# PAPR_STM32G031J6_V1.net
KiCad netlist of a schematic drawn in EasyEDA
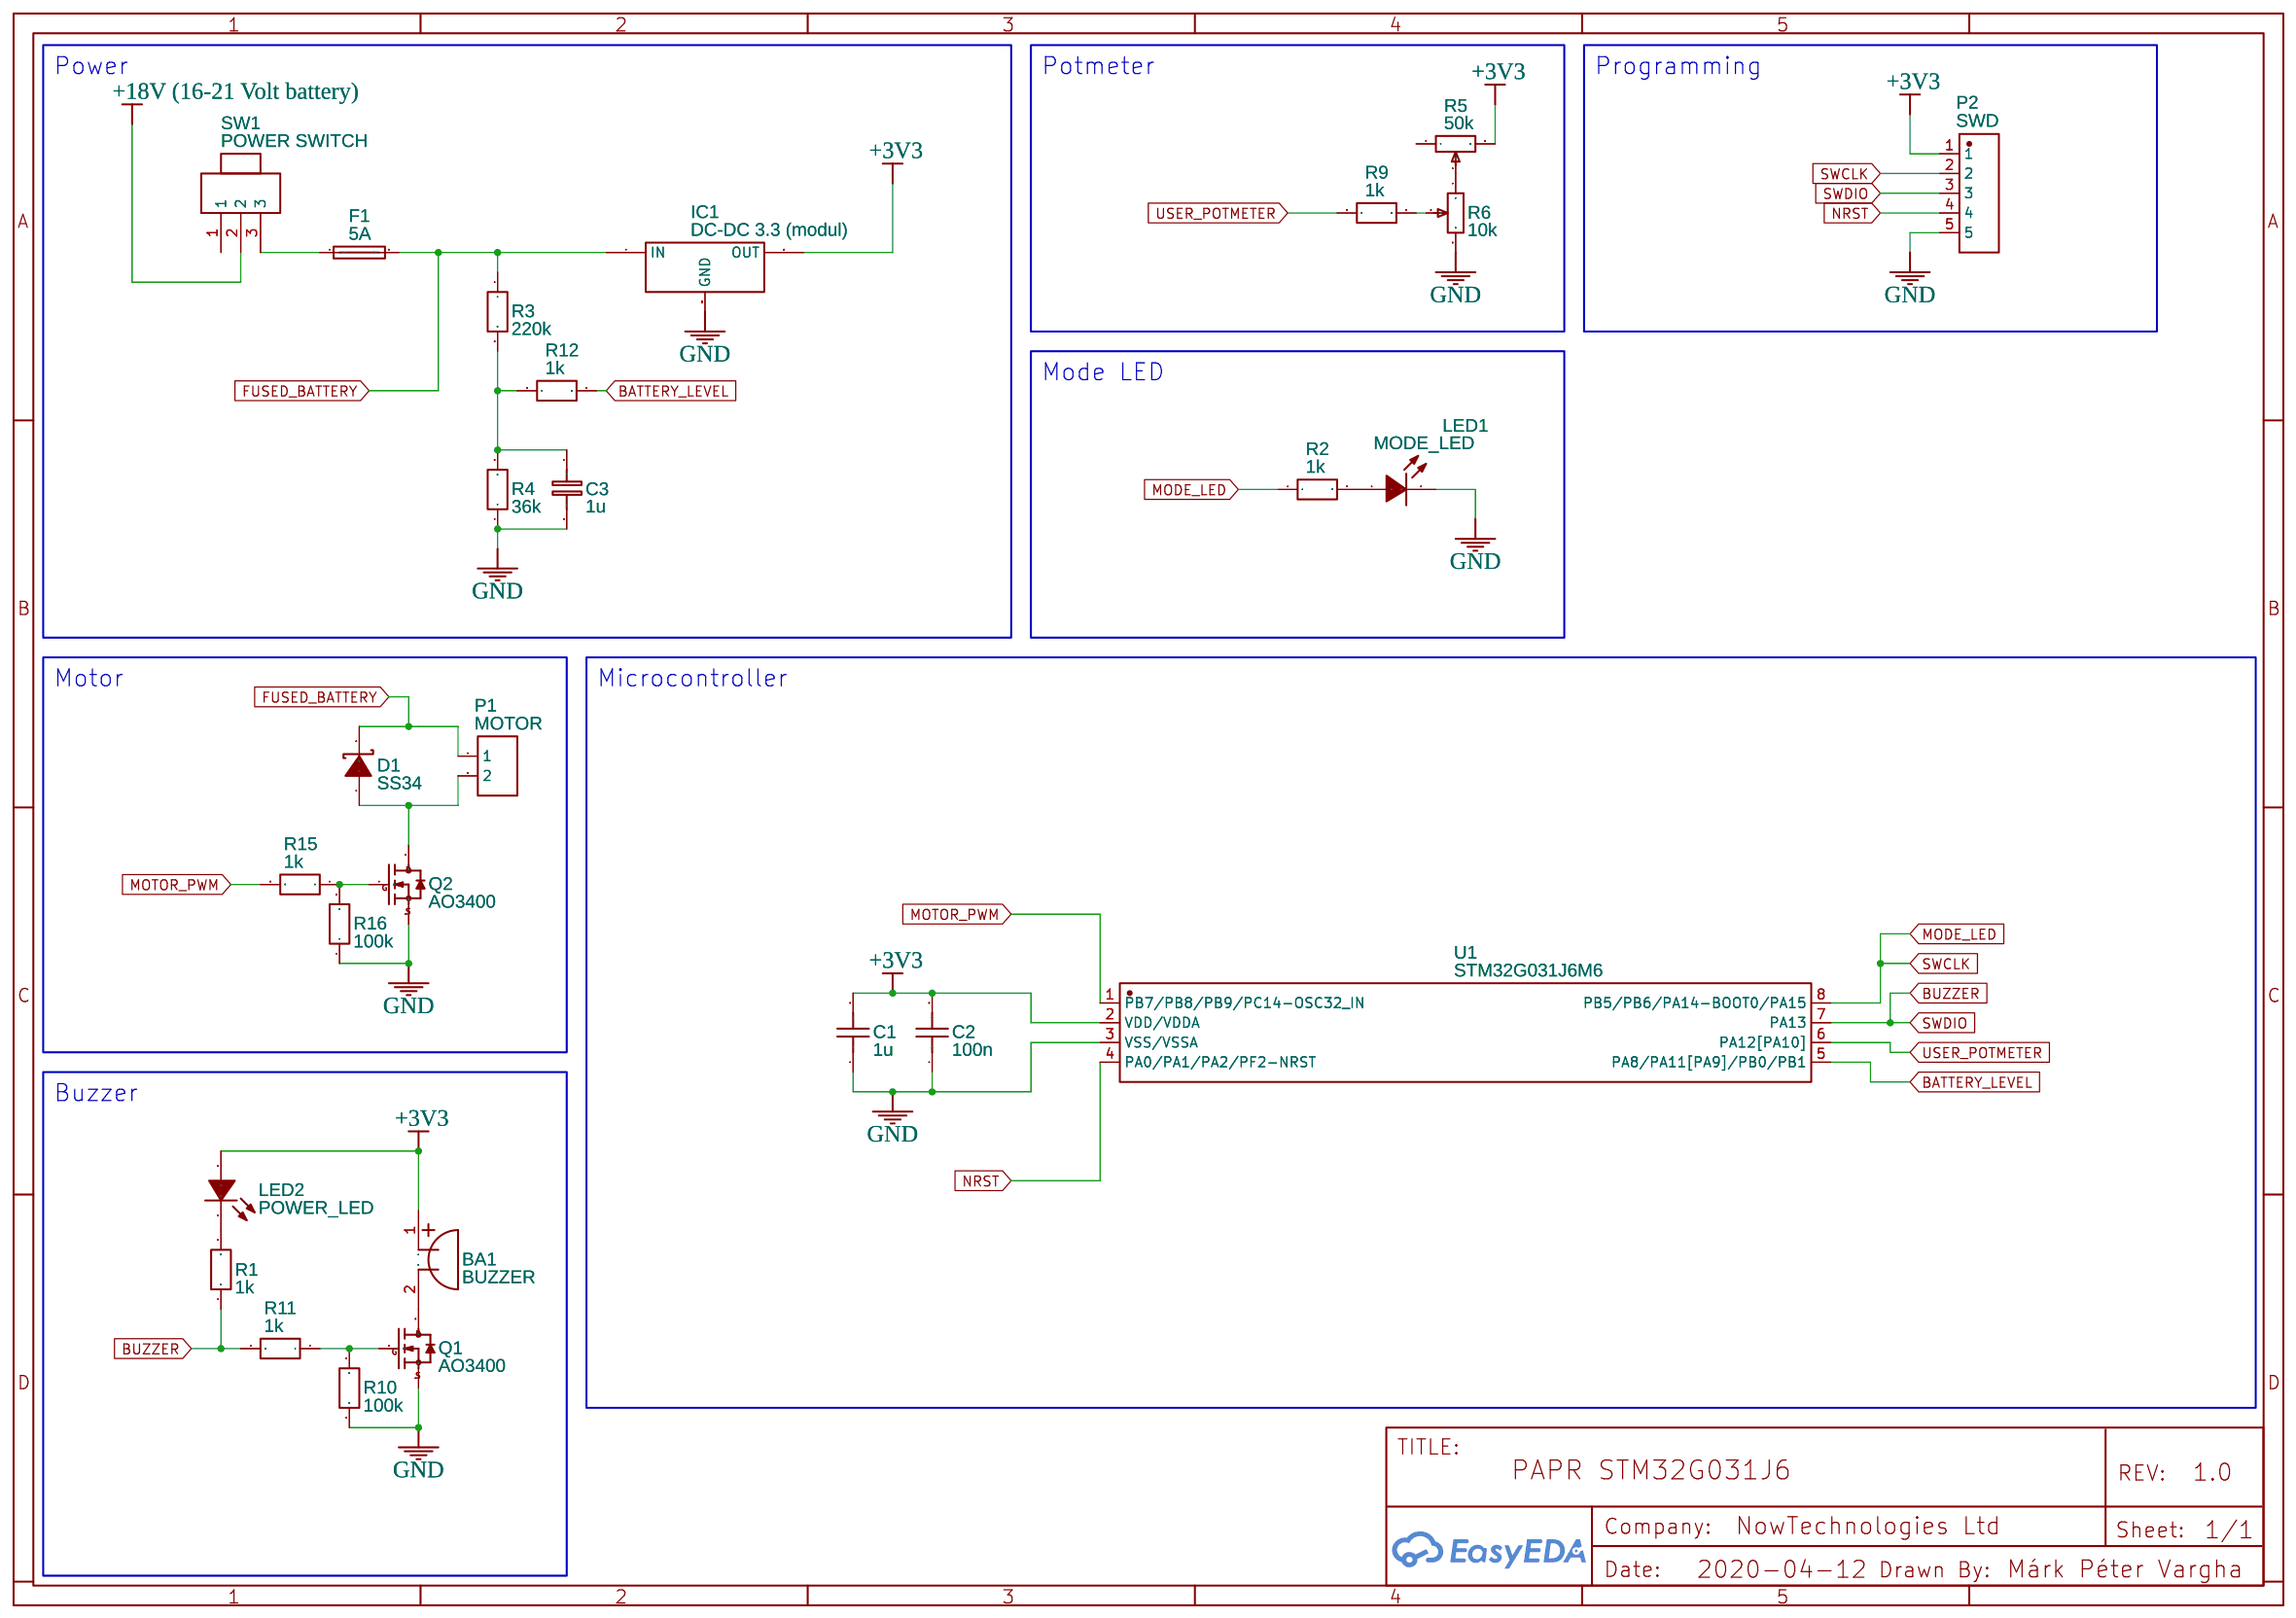
[diagram p0: schematic sheet]

(export (version "E")
  (design (tool "Eeschema 10.0.6"))
  (components
    (comp (ref "BA1") (value "BUZZER") (libsource (lib "") (part "9X5.5_BEEPER_5V")))
    (comp (ref "C1") (value "1u") (libsource (lib "") (part "Cap_RAD-0.1_US")))
    (comp (ref "C2") (value "100n") (libsource (lib "") (part "Cap_RAD-0.1_US")))
    (comp (ref "C3") (value "1u") (libsource (lib "") (part "Cap_RAD-0.1_EU")))
    (comp (ref "D1")
      (value "SS34")
      (fields (field (name "BOM_Supplier Part") "C13763"))
      (libsource (lib "") (part "SS34"))
    )
    (comp (ref "F1")
      (value "5A")
      (fields
        (field (name "BOM_Manufacturer Part") "5F 5A 250VACGlass tube fuse")
        (field (name "BOM_Supplier Part") "C3120")
      )
      (libsource (lib "") (part "5F 5A 250VACGlass tube fuse"))
    )
    (comp (ref "IC1") (value "DC-DC 3.3 (modul)") (libsource (lib "") (part "AMS1117 3.3")))
    (comp (ref "LED1")
      (value "MODE_LED")
      (fields
        (field (name "BOM_Manufacturer Part") "204-10SURD/S530-A3")
        (field (name "BOM_Supplier Part") "C99772")
      )
      (libsource (lib "") (part "204-10SURD/S530-A3_1"))
    )
    (comp (ref "LED2")
      (value "POWER_LED")
      (fields
        (field (name "BOM_Manufacturer Part") "204-10SURD/S530-A3")
        (field (name "BOM_Supplier Part") "C99772")
      )
      (libsource (lib "") (part "204-10SURD/S530-A3"))
    )
    (comp (ref "P1")
      (value "MOTOR")
      (fields
        (field (name "BOM_Manufacturer Part") "2.54-1*2PFemale")
        (field (name "BOM_Supplier Part") "C49661")
      )
      (libsource (lib "") (part "Header-Female-2.54_1x2"))
    )
    (comp (ref "P2")
      (value "SWD")
      (fields
        (field (name "BOM_Manufacturer Part") "Female header1*5P")
        (field (name "BOM_Supplier Part") "C66508")
      )
      (libsource (lib "") (part "Female header1*5P"))
    )
    (comp (ref "Q1")
      (value "AO3400")
      (fields (field (name "BOM_Supplier Part") "C122850"))
      (libsource (lib "") (part "AO3400_C122850"))
    )
    (comp (ref "Q2")
      (value "AO3400")
      (fields (field (name "BOM_Supplier Part") "C122850"))
      (libsource (lib "") (part "AO3400_C122850"))
    )
    (comp (ref "R1") (value "1k") (libsource (lib "") (part "Res_AXIAL-0.3(1/8W)_EU_1")))
    (comp (ref "R2") (value "1k") (libsource (lib "") (part "Res_AXIAL-0.3(1/8W)_EU_2")))
    (comp (ref "R3") (value "220k") (libsource (lib "") (part "Res_AXIAL-0.3(1/8W)_EU_3")))
    (comp (ref "R4") (value "36k") (libsource (lib "") (part "Res_AXIAL-0.3(1/8W)_EU_1")))
    (comp (ref "R5")
      (value "50k")
      (fields
        (field (name "BOM_Manufacturer Part") "3386P-1-101LF")
        (field (name "BOM_Supplier Part") "C125022")
      )
      (libsource (lib "") (part "potmeter"))
    )
    (comp (ref "R6")
      (value "10k")
      (fields
        (field (name "BOM_Manufacturer Part") "3386P-1-101LF")
        (field (name "BOM_Supplier Part") "C125022")
      )
      (libsource (lib "") (part "potmeter_1"))
    )
    (comp (ref "R9") (value "1k") (libsource (lib "") (part "Res_AXIAL-0.3(1/8W)_EU_2")))
    (comp (ref "R10") (value "100k") (libsource (lib "") (part "Res_AXIAL-0.3(1/8W)_EU_1")))
    (comp (ref "R11") (value "1k") (libsource (lib "") (part "Res_AXIAL-0.3(1/8W)_EU")))
    (comp (ref "R12") (value "1k") (libsource (lib "") (part "Res_AXIAL-0.3(1/8W)_EU_2")))
    (comp (ref "R15") (value "1k") (libsource (lib "") (part "Res_AXIAL-0.3(1/8W)_EU")))
    (comp (ref "R16") (value "100k") (libsource (lib "") (part "Res_AXIAL-0.3(1/8W)_EU_1")))
    (comp (ref "SW1")
      (value "POWER SWITCH")
      (fields
        (field (name "BOM_Manufacturer Part") "Rocker switch601-10211BB")
        (field (name "BOM_Supplier Part") "C67849")
      )
      (libsource (lib "") (part "Rocker switch601-10211BB"))
    )
    (comp (ref "U1")
      (value "STM32G031J6M6")
      (fields (field (name "BOM_Supplier Part") "C432201"))
      (libsource (lib "") (part "STM32G031J6M6"))
    )
  )
  (nets
    (net (code "1") (name "+3V3") (class "Default")
      (node (ref "BA1") (pin "1") (pinfunction "1_1") (pintype "unspecified"))
      (node (ref "C1") (pin "2") (pinfunction "2_2") (pintype "unspecified"))
      (node (ref "C2") (pin "2") (pinfunction "2_2") (pintype "unspecified"))
      (node (ref "IC1") (pin "OUT") (pinfunction "OUT_OUT") (pintype "unspecified"))
      (node (ref "LED2") (pin "1") (pinfunction "A_1") (pintype "unspecified"))
      (node (ref "P2") (pin "1") (pinfunction "1_1") (pintype "unspecified"))
      (node (ref "R5") (pin "3") (pinfunction "3_3") (pintype "input"))
      (node (ref "U1") (pin "2") (pinfunction "VDD/VDDA_2") (pintype "unspecified"))
    )
    (net (code "2") (name "+18V (16-21 Volt battery)") (class "Default")
      (node (ref "SW1") (pin "2") (pinfunction "2_2") (pintype "unspecified"))
    )
    (net (code "3") (name "BATTERY_LEVEL") (class "Default")
      (node (ref "R12") (pin "2") (pinfunction "2_2") (pintype "unspecified"))
      (node (ref "U1") (pin "5") (pinfunction "PA8/PA11[PA9]/PB0/PB1_5") (pintype "unspecified"))
    )
    (net (code "4") (name "BUZZER") (class "Default")
      (node (ref "P2") (pin "3") (pinfunction "3_3") (pintype "unspecified"))
      (node (ref "R1") (pin "1") (pinfunction "1_1") (pintype "unspecified"))
      (node (ref "R11") (pin "2") (pinfunction "2_2") (pintype "unspecified"))
      (node (ref "U1") (pin "7") (pinfunction "PA13_7") (pintype "unspecified"))
    )
    (net (code "5") (name "FUSED_BATTERY") (class "Default")
      (node (ref "D1") (pin "2") (pinfunction "K_2") (pintype "unspecified"))
      (node (ref "F1") (pin "2") (pinfunction "2_2") (pintype "unspecified"))
      (node (ref "IC1") (pin "IN") (pinfunction "IN_IN") (pintype "input"))
      (node (ref "P1") (pin "1") (pinfunction "1_1") (pintype "input"))
      (node (ref "R3") (pin "1") (pinfunction "1_1") (pintype "unspecified"))
    )
    (net (code "6") (name "GND") (class "Default")
      (node (ref "C1") (pin "1") (pinfunction "1_1") (pintype "unspecified"))
      (node (ref "C2") (pin "1") (pinfunction "1_1") (pintype "unspecified"))
      (node (ref "C3") (pin "2") (pinfunction "2_2") (pintype "unspecified"))
      (node (ref "IC1") (pin "GND") (pinfunction "GND_GND") (pintype "input"))
      (node (ref "LED1") (pin "2") (pinfunction "K_2") (pintype "unspecified"))
      (node (ref "P2") (pin "5") (pinfunction "5_5") (pintype "unspecified"))
      (node (ref "Q1") (pin "2") (pinfunction "S_2") (pintype "unspecified"))
      (node (ref "Q2") (pin "2") (pinfunction "S_2") (pintype "unspecified"))
      (node (ref "R10") (pin "1") (pinfunction "1_1") (pintype "unspecified"))
      (node (ref "R16") (pin "1") (pinfunction "1_1") (pintype "unspecified"))
      (node (ref "R4") (pin "1") (pinfunction "1_1") (pintype "unspecified"))
      (node (ref "R6") (pin "3") (pinfunction "3_3") (pintype "input"))
      (node (ref "U1") (pin "3") (pinfunction "VSS/VSSA_3") (pintype "unspecified"))
    )
    (net (code "7") (name "MODE_LED") (class "Default")
      (node (ref "P2") (pin "2") (pinfunction "2_2") (pintype "unspecified"))
      (node (ref "R2") (pin "1") (pinfunction "1_1") (pintype "unspecified"))
      (node (ref "U1") (pin "8") (pinfunction "PB5/PB6/PA14-BOOT0/PA15_8") (pintype "unspecified"))
    )
    (net (code "8") (name "MOTOR_PWM") (class "Default")
      (node (ref "R15") (pin "2") (pinfunction "2_2") (pintype "unspecified"))
      (node (ref "U1") (pin "1") (pinfunction "PB7/PB8/PB9/PC14-OSC32_IN_1") (pintype "unspecified"))
    )
    (net (code "9") (name "NRST") (class "Default")
      (node (ref "P2") (pin "4") (pinfunction "4_4") (pintype "unspecified"))
      (node (ref "U1") (pin "4") (pinfunction "PA0/PA1/PA2/PF2-NRST_4") (pintype "unspecified"))
    )
    (net (code "10") (name "Net-(C3-Pad1)") (class "Default")
      (node (ref "C3") (pin "1") (pinfunction "1_1") (pintype "unspecified"))
      (node (ref "R12") (pin "1") (pinfunction "1_1") (pintype "unspecified"))
      (node (ref "R3") (pin "2") (pinfunction "2_2") (pintype "unspecified"))
      (node (ref "R4") (pin "2") (pinfunction "2_2") (pintype "unspecified"))
    )
    (net (code "11") (name "Net-(D1-A)") (class "Default")
      (node (ref "D1") (pin "1") (pinfunction "A_1") (pintype "unspecified"))
      (node (ref "P1") (pin "2") (pinfunction "2_2") (pintype "input"))
      (node (ref "Q2") (pin "3") (pinfunction "D_3") (pintype "unspecified"))
    )
    (net (code "12") (name "Net-(F1-Pad1)") (class "Default")
      (node (ref "F1") (pin "1") (pinfunction "1_1") (pintype "unspecified"))
      (node (ref "SW1") (pin "3") (pinfunction "3_3") (pintype "unspecified"))
    )
    (net (code "13") (name "Net-(LED1-A)") (class "Default")
      (node (ref "LED1") (pin "1") (pinfunction "A_1") (pintype "unspecified"))
      (node (ref "R2") (pin "2") (pinfunction "2_2") (pintype "unspecified"))
    )
    (net (code "14") (name "Net-(LED2-K)") (class "Default")
      (node (ref "LED2") (pin "2") (pinfunction "K_2") (pintype "unspecified"))
      (node (ref "R1") (pin "2") (pinfunction "2_2") (pintype "unspecified"))
    )
    (net (code "15") (name "Net-(Q1-D)") (class "Default")
      (node (ref "BA1") (pin "2") (pinfunction "2_2") (pintype "unspecified"))
      (node (ref "Q1") (pin "3") (pinfunction "D_3") (pintype "unspecified"))
    )
    (net (code "16") (name "Net-(Q1-G)") (class "Default")
      (node (ref "Q1") (pin "1") (pinfunction "G_1") (pintype "unspecified"))
      (node (ref "R10") (pin "2") (pinfunction "2_2") (pintype "unspecified"))
      (node (ref "R11") (pin "1") (pinfunction "1_1") (pintype "unspecified"))
    )
    (net (code "17") (name "Net-(Q2-G)") (class "Default")
      (node (ref "Q2") (pin "1") (pinfunction "G_1") (pintype "unspecified"))
      (node (ref "R15") (pin "1") (pinfunction "1_1") (pintype "unspecified"))
      (node (ref "R16") (pin "2") (pinfunction "2_2") (pintype "unspecified"))
    )
    (net (code "18") (name "Net-(R5-Pad2)") (class "Default")
      (node (ref "R5") (pin "2") (pinfunction "2_2") (pintype "input"))
      (node (ref "R6") (pin "1") (pinfunction "1_1") (pintype "input"))
    )
    (net (code "19") (name "Net-(R6-Pad2)") (class "Default")
      (node (ref "R6") (pin "2") (pinfunction "2_2") (pintype "input"))
      (node (ref "R9") (pin "2") (pinfunction "2_2") (pintype "unspecified"))
    )
    (net (code "20") (name "USER_POTMETER") (class "Default")
      (node (ref "R9") (pin "1") (pinfunction "1_1") (pintype "unspecified"))
      (node (ref "U1") (pin "6") (pinfunction "PA12[PA10]_6") (pintype "unspecified"))
    )
    (net (code "21") (name "unconnected-(R5-Pad1)") (class "Default")
      (node (ref "R5") (pin "1") (pinfunction "1_1") (pintype "input"))
    )
    (net (code "22") (name "unconnected-(SW1-Pad1)") (class "Default")
      (node (ref "SW1") (pin "1") (pinfunction "1_1") (pintype "unspecified"))
    )
  )
)
